# rev2.net
KiCad netlist of a schematic drawn in EAGLE
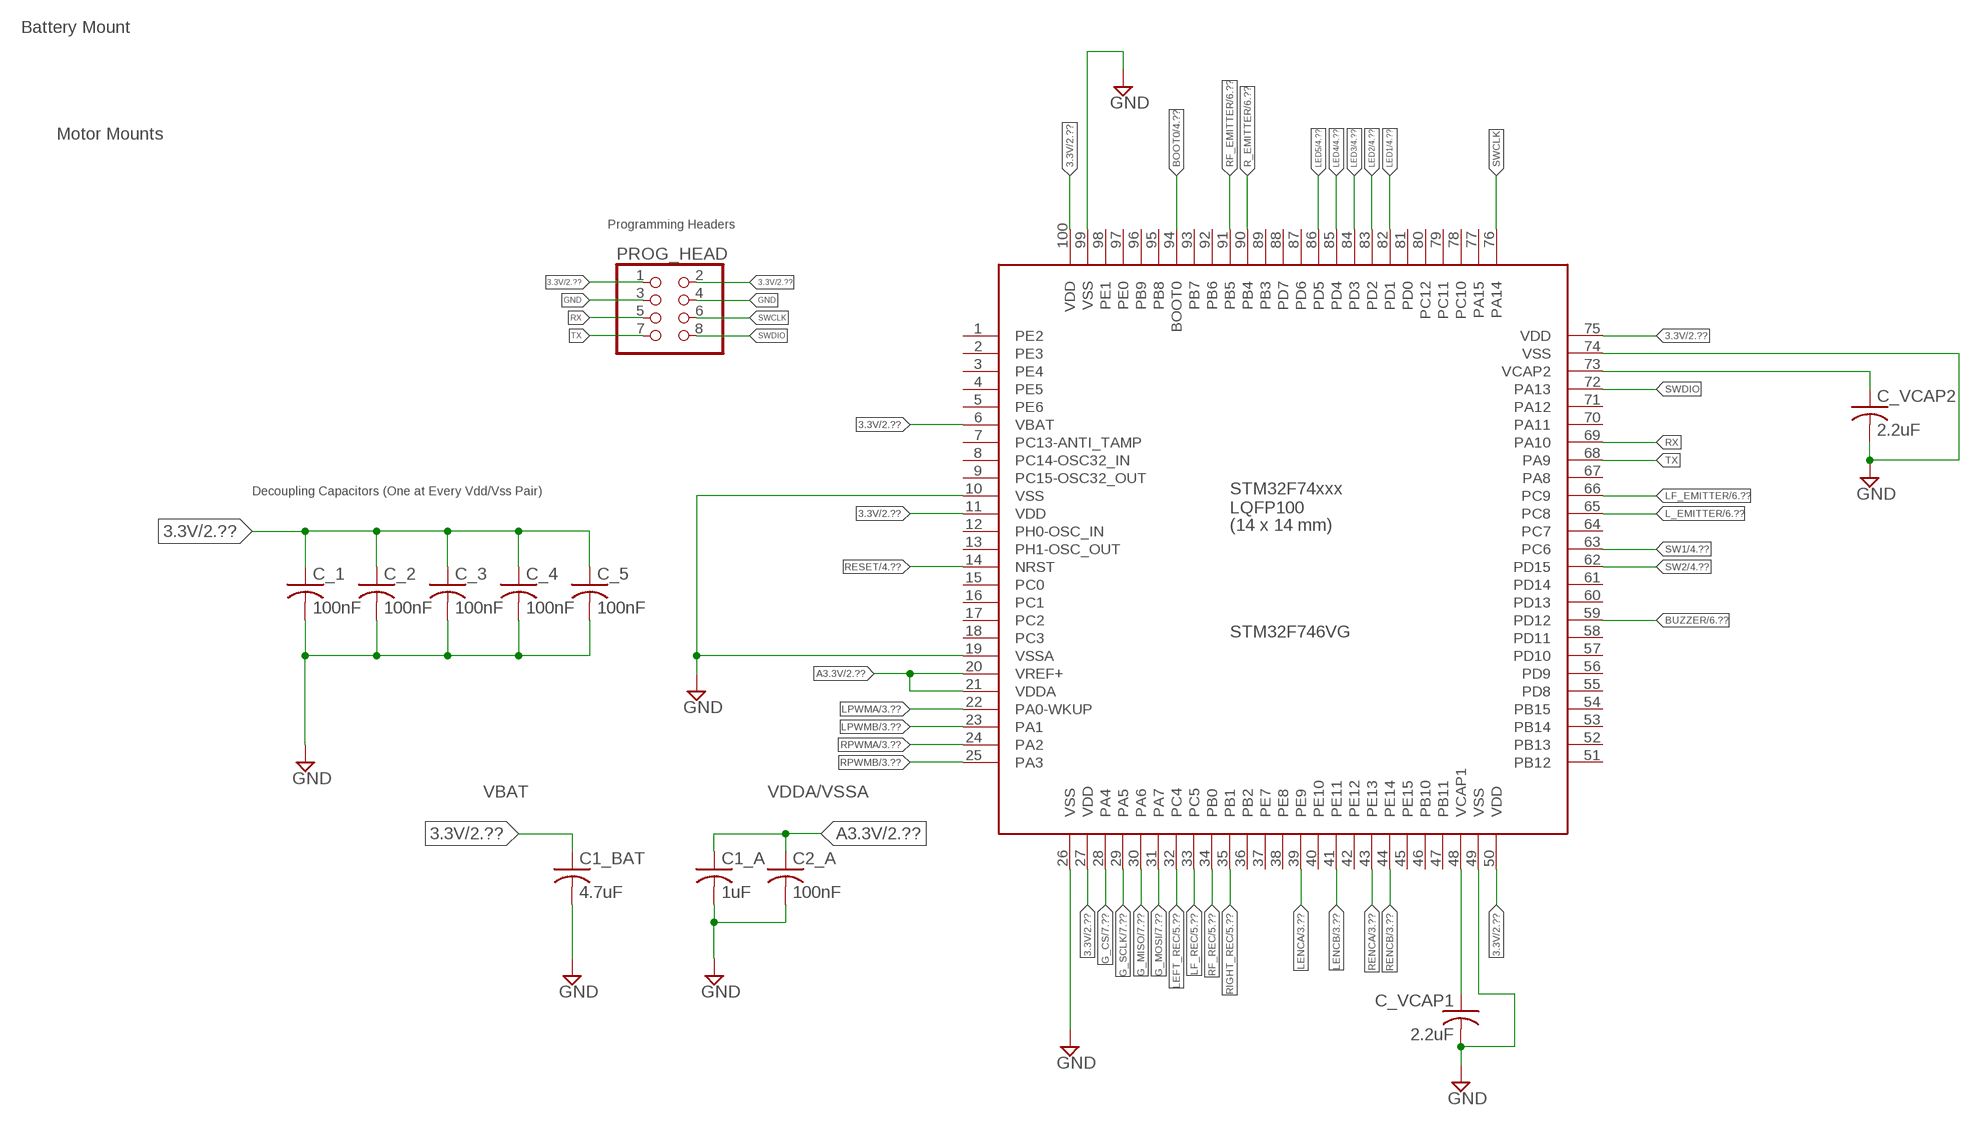
[diagram p0: schematic, sheet 1]
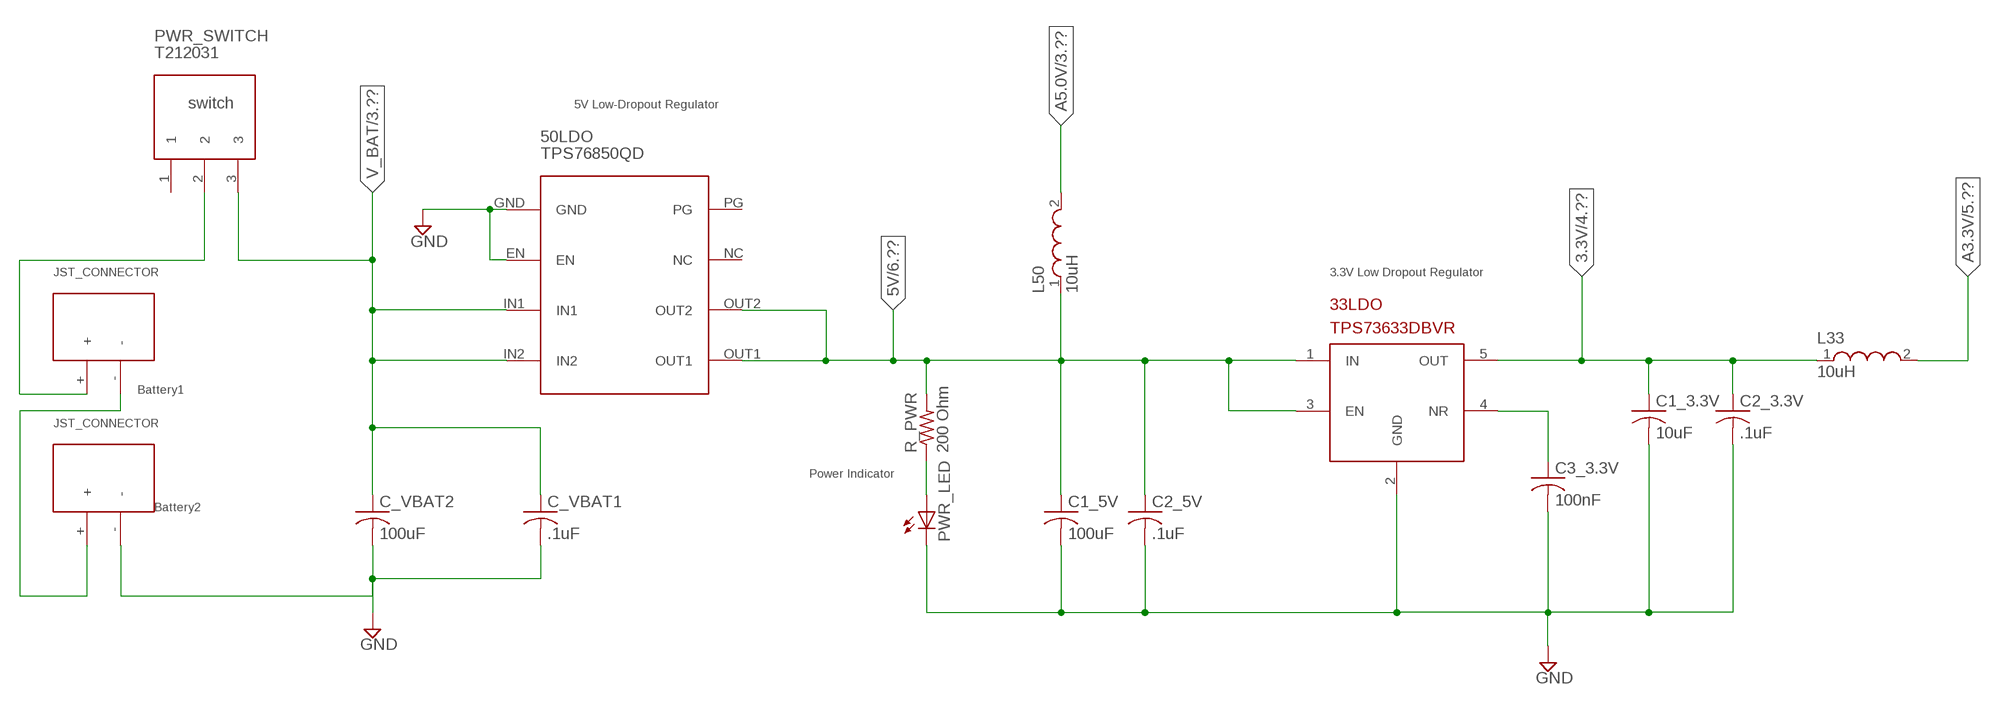
[diagram p1: schematic, sheet 2]
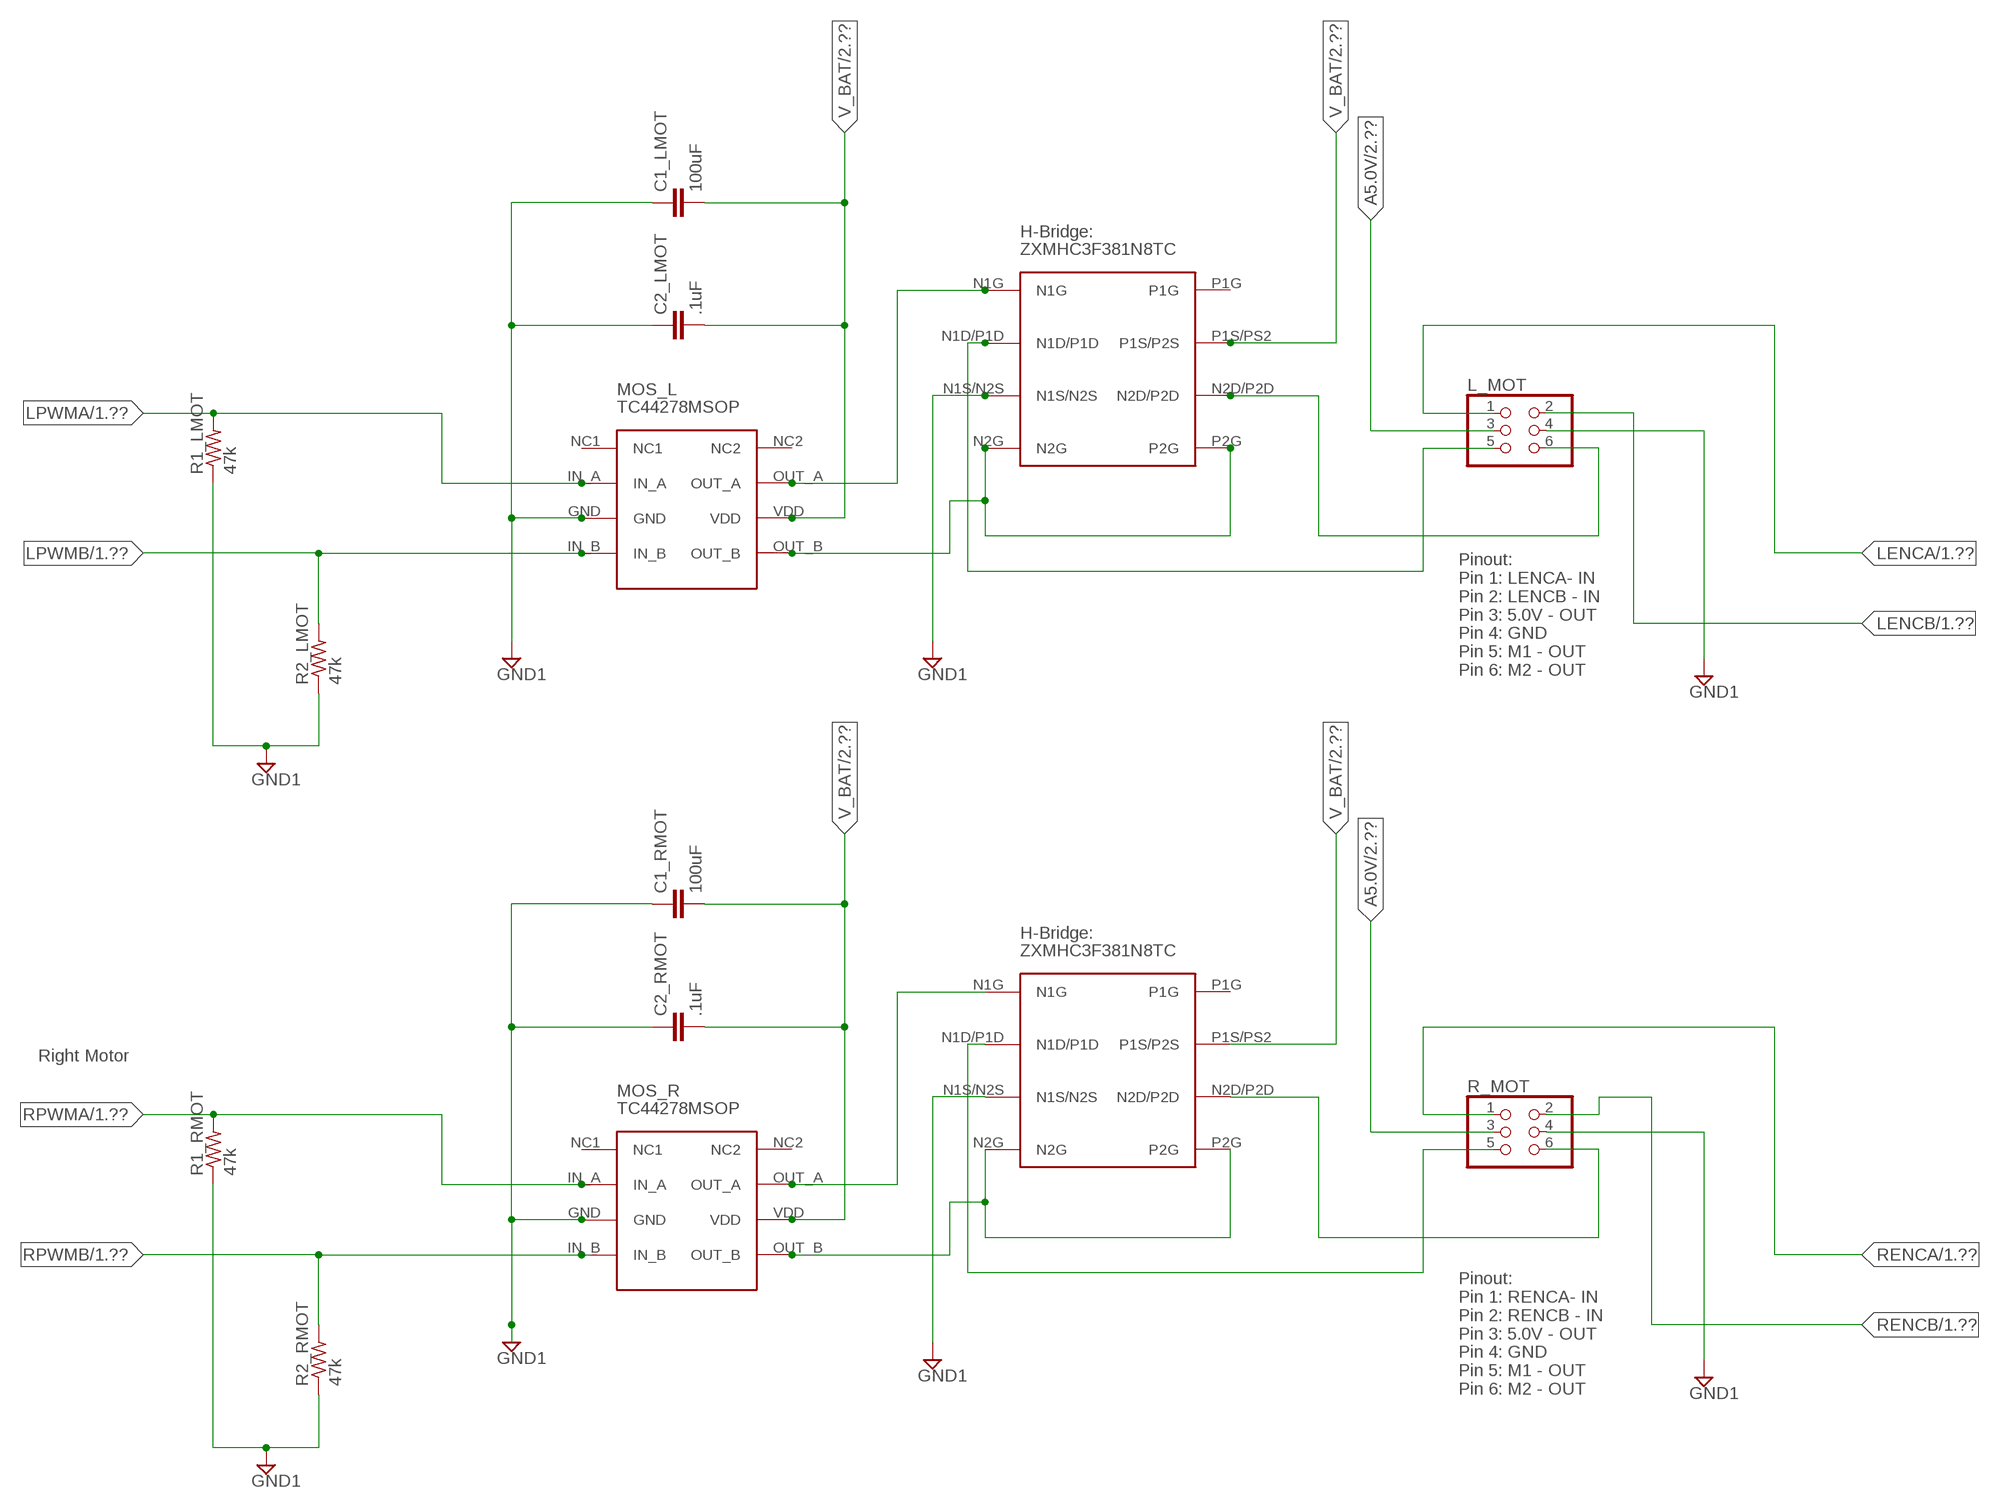
[diagram p2: schematic, sheet 3]
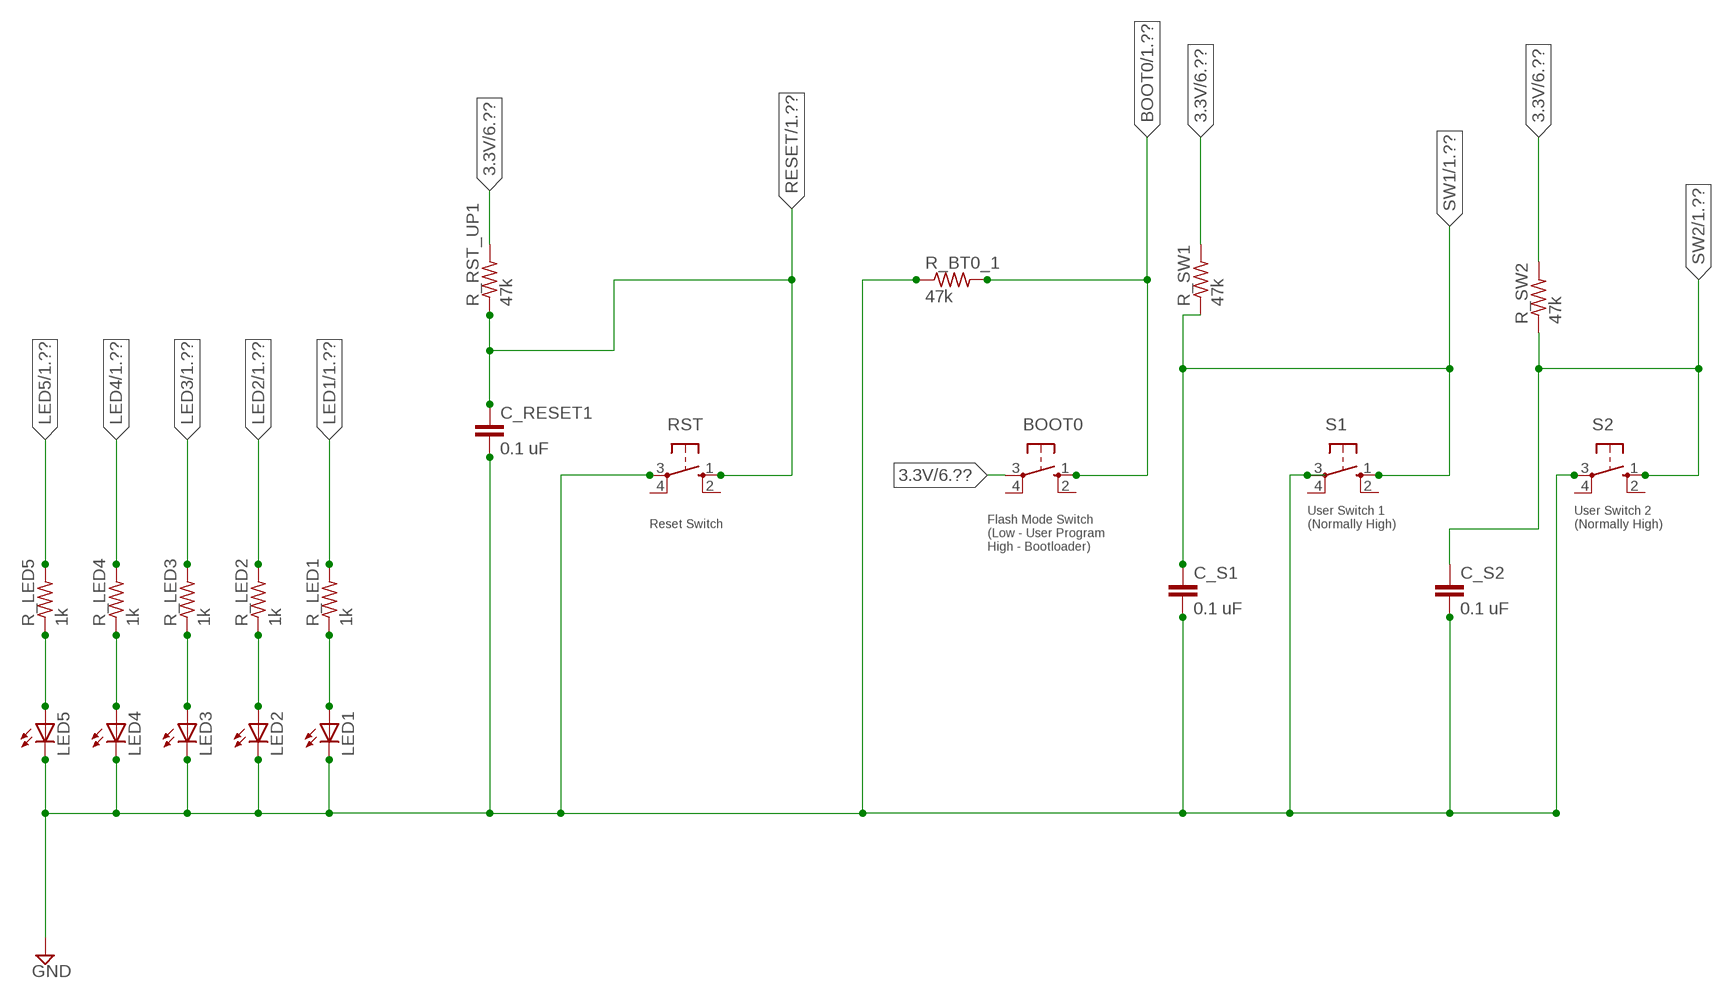
[diagram p3: schematic, sheet 4]
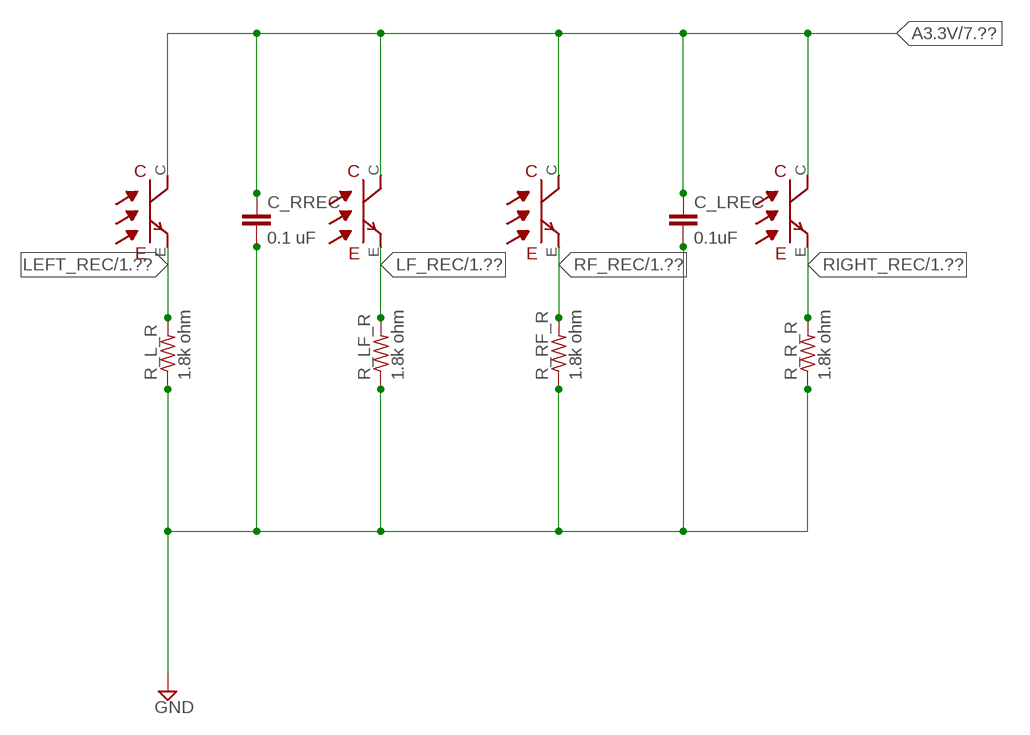
[diagram p4: schematic, sheet 5]
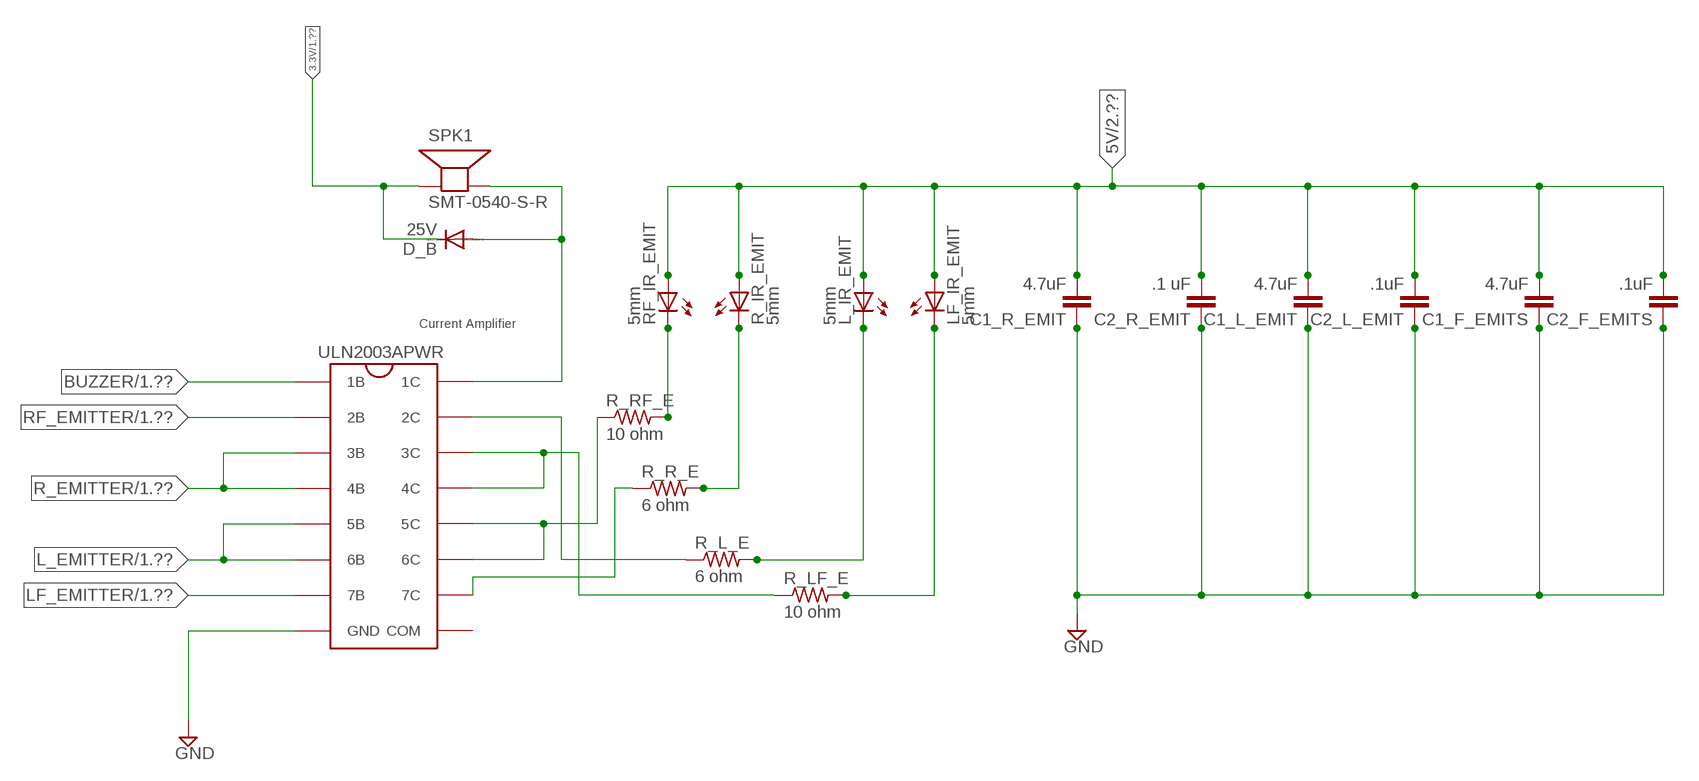
[diagram p5: schematic, sheet 6]
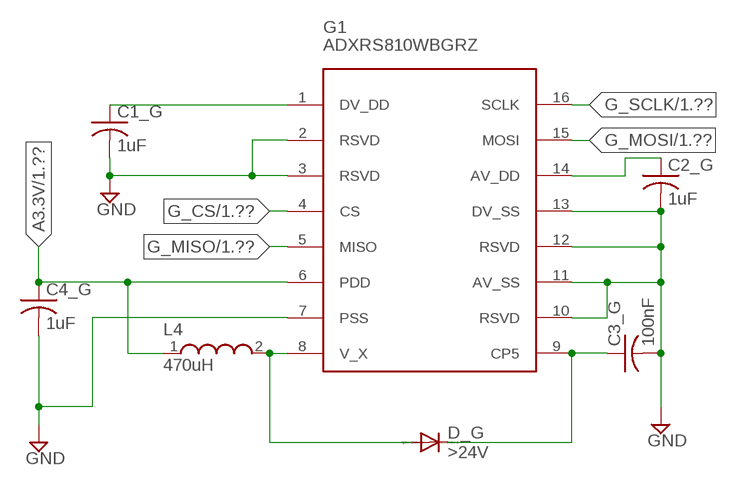
[diagram p6: schematic, sheet 7]

(export (version "E")
  (design (tool "Eeschema 10.0.6"))
  (components
    (comp (ref "C1_LMOT")
      (value "100uF")
      (footprint "eagle-import:C0805")
      (libsource (lib "eagle-import") (part "C-EUC0805"))
    )
    (comp (ref "C1_RMOT")
      (value "100uF")
      (footprint "eagle-import:C0805")
      (libsource (lib "eagle-import") (part "C-EUC0805"))
    )
    (comp (ref "C2_LMOT")
      (value ".1uF")
      (footprint "eagle-import:C0805")
      (libsource (lib "eagle-import") (part "C-EUC0805"))
    )
    (comp (ref "C2_RMOT")
      (value ".1uF")
      (footprint "eagle-import:C0805")
      (libsource (lib "eagle-import") (part "C-EUC0805"))
    )
    (comp (ref "HB_L")
      (value "ZXMHC3F381N8TC")
      (footprint "eagle-import:8-SOIC")
      (libsource (lib "eagle-import") (part "ZXMHC3F381N8TC"))
    )
    (comp (ref "HB_R")
      (value "ZXMHC3F381N8TC")
      (footprint "eagle-import:8-SOIC")
      (libsource (lib "eagle-import") (part "ZXMHC3F381N8TC"))
    )
    (comp (ref "L_MOT")
      (value "PINHD-2X3")
      (footprint "eagle-import:2X03")
      (libsource (lib "eagle-import") (part "PINHD-2X3"))
    )
    (comp (ref "MOS_L")
      (value "TC44278MSOP")
      (footprint "eagle-import:TC44278MSOP")
      (libsource (lib "eagle-import") (part "TC44278MSOP"))
    )
    (comp (ref "MOS_R")
      (value "TC44278MSOP")
      (footprint "eagle-import:TC44278MSOP")
      (libsource (lib "eagle-import") (part "TC44278MSOP"))
    )
    (comp (ref "R1_LMOT")
      (value "47k")
      (footprint "eagle-import:R0603")
      (libsource (lib "eagle-import") (part "R-US_R0603"))
    )
    (comp (ref "R1_RMOT")
      (value "47k")
      (footprint "eagle-import:R0603")
      (libsource (lib "eagle-import") (part "R-US_R0603"))
    )
    (comp (ref "R2_LMOT")
      (value "47k")
      (footprint "eagle-import:R0603")
      (libsource (lib "eagle-import") (part "R-US_R0603"))
    )
    (comp (ref "R2_RMOT")
      (value "47k")
      (footprint "eagle-import:R0603")
      (libsource (lib "eagle-import") (part "R-US_R0603"))
    )
    (comp (ref "R_MOT")
      (value "PINHD-2X3")
      (footprint "eagle-import:2X03")
      (libsource (lib "eagle-import") (part "PINHD-2X3"))
    )
    (comp (ref "C1_F_EMITS")
      (value "4.7uF")
      (footprint "eagle-import:C0603")
      (libsource (lib "eagle-import") (part "resistor_C-EUC0603"))
    )
    (comp (ref "C1_L_EMIT")
      (value "4.7uF")
      (footprint "eagle-import:C0603")
      (libsource (lib "eagle-import") (part "resistor_C-EUC0603"))
    )
    (comp (ref "C1_R_EMIT")
      (value "4.7uF")
      (footprint "eagle-import:C0603")
      (libsource (lib "eagle-import") (part "resistor_C-EUC0603"))
    )
    (comp (ref "C2_F_EMITS")
      (value ".1uF")
      (footprint "eagle-import:C0603")
      (libsource (lib "eagle-import") (part "resistor_C-EUC0603"))
    )
    (comp (ref "C2_L_EMIT")
      (value ".1uF")
      (footprint "eagle-import:C0603")
      (libsource (lib "eagle-import") (part "resistor_C-EUC0603"))
    )
    (comp (ref "C2_R_EMIT")
      (value ".1 uF")
      (footprint "eagle-import:C0603")
      (libsource (lib "eagle-import") (part "resistor_C-EUC0603"))
    )
    (comp (ref "D_B")
      (value "25V")
      (footprint "eagle-import:SOD123")
      (libsource (lib "eagle-import") (part "DIODE-SOD123"))
    )
    (comp (ref "LF_IR_EMIT")
      (value "5mm")
      (footprint "eagle-import:LED5MM")
      (libsource (lib "eagle-import") (part "LED5MM"))
    )
    (comp (ref "L_IR_EMIT")
      (value "5mm")
      (footprint "eagle-import:LED5MM")
      (libsource (lib "eagle-import") (part "LED5MM"))
    )
    (comp (ref "RF_IR_EMIT")
      (value "5mm")
      (footprint "eagle-import:LED5MM")
      (libsource (lib "eagle-import") (part "LED5MM"))
    )
    (comp (ref "R_IR_EMIT")
      (value "5mm")
      (footprint "eagle-import:LED5MM")
      (libsource (lib "eagle-import") (part "LED5MM"))
    )
    (comp (ref "R_LF_E")
      (value "10 ohm")
      (footprint "eagle-import:R0603")
      (libsource (lib "eagle-import") (part "R-US_R0603"))
    )
    (comp (ref "R_L_E")
      (value "6 ohm")
      (footprint "eagle-import:R0603")
      (libsource (lib "eagle-import") (part "R-US_R0603"))
    )
    (comp (ref "R_RF_E")
      (value "10 ohm")
      (footprint "eagle-import:R0603")
      (libsource (lib "eagle-import") (part "R-US_R0603"))
    )
    (comp (ref "R_R_E")
      (value "6 ohm")
      (footprint "eagle-import:R0603")
      (libsource (lib "eagle-import") (part "R-US_R0603"))
    )
    (comp (ref "SPK1")
      (value "SMT-0540-S-R")
      (footprint "eagle-import:SMT-0540-S-R")
      (fields (field (name "MF") "PUI Audio"))
      (libsource (lib "eagle-import") (part "SMT-0540-S-R"))
    )
    (comp (ref "U$9")
      (value "ULN2003APWR")
      (footprint "eagle-import:ULN2003APWR")
      (libsource (lib "eagle-import") (part "ULN2003APWR"))
    )
    (comp (ref "33LDO")
      (value "TPS73633DBVR")
      (footprint "eagle-import:SOT23-DBV")
      (fields (field (name "MF") "Texas Instruments"))
      (libsource (lib "eagle-import") (part "TPS73633DBVR"))
    )
    (comp (ref "50LDO")
      (value "TPS76850QD")
      (footprint "eagle-import:8-SOIC(SMT)")
      (libsource (lib "eagle-import") (part "TPS76850"))
    )
    (comp (ref "C1_3.3V")
      (value "10uF")
      (footprint "eagle-import:C0603")
      (libsource (lib "eagle-import") (part "resistor_C-USC0603"))
    )
    (comp (ref "C1_5V")
      (value "100uF")
      (footprint "eagle-import:C0603")
      (libsource (lib "eagle-import") (part "resistor_C-USC0603"))
    )
    (comp (ref "C2_3.3V")
      (value ".1uF")
      (footprint "eagle-import:C0603")
      (libsource (lib "eagle-import") (part "resistor_C-USC0603"))
    )
    (comp (ref "C2_5V")
      (value ".1uF")
      (footprint "eagle-import:C0603")
      (libsource (lib "eagle-import") (part "resistor_C-USC0603"))
    )
    (comp (ref "C3_3.3V")
      (value "100nF")
      (footprint "eagle-import:C0603")
      (libsource (lib "eagle-import") (part "resistor_C-USC0603"))
    )
    (comp (ref "C_VBAT1")
      (value ".1uF")
      (footprint "eagle-import:C0603")
      (libsource (lib "eagle-import") (part "resistor_C-USC0603"))
    )
    (comp (ref "C_VBAT2")
      (value "100uF")
      (footprint "eagle-import:C1206")
      (libsource (lib "eagle-import") (part "resistor_C-USC1206"))
    )
    (comp (ref "L33")
      (value "10uH")
      (footprint "eagle-import:WE-MI_0805")
      (libsource (lib "eagle-import") (part "WE-MI_0805"))
    )
    (comp (ref "L50")
      (value "10uH")
      (footprint "eagle-import:WE-MI_0805")
      (libsource (lib "eagle-import") (part "WE-MI_0805"))
    )
    (comp (ref "PWR_LED")
      (value "LEDCHIPLED_0805")
      (footprint "eagle-import:CHIPLED_0805")
      (libsource (lib "eagle-import") (part "LEDCHIPLED_0805"))
    )
    (comp (ref "PWR_SWITCH")
      (value "T212031")
      (footprint "eagle-import:T212031")
      (libsource (lib "eagle-import") (part "T212031"))
    )
    (comp (ref "R_PWR")
      (value "200 Ohm")
      (footprint "eagle-import:R0603")
      (libsource (lib "eagle-import") (part "R-US_R0603"))
    )
    (comp (ref "U$7")
      (value "JST_CONNECTOR_FEMALE")
      (footprint "eagle-import:JST_CONNECTOR_FEMALE")
      (libsource (lib "eagle-import") (part "JST_CONNECTOR_FEMALE"))
    )
    (comp (ref "U$8")
      (value "JST_CONNECTOR_FEMALE")
      (footprint "eagle-import:JST_CONNECTOR_FEMALE")
      (libsource (lib "eagle-import") (part "JST_CONNECTOR_FEMALE"))
    )
    (comp (ref "C_LREC")
      (value "0.1uF")
      (footprint "eagle-import:C0603")
      (libsource (lib "eagle-import") (part "resistor_C-EUC0603"))
    )
    (comp (ref "C_RREC")
      (value "0.1 uF")
      (footprint "eagle-import:C0603")
      (libsource (lib "eagle-import") (part "resistor_C-EUC0603"))
    )
    (comp (ref "LF_REC")
      (value "RECEIVER")
      (footprint "eagle-import:RECEIVER")
      (libsource (lib "eagle-import") (part "RECEIVER"))
    )
    (comp (ref "L_REC")
      (value "RECEIVER")
      (footprint "eagle-import:RECEIVER")
      (libsource (lib "eagle-import") (part "RECEIVER"))
    )
    (comp (ref "RF_REC")
      (value "RECEIVER")
      (footprint "eagle-import:RECEIVER")
      (libsource (lib "eagle-import") (part "RECEIVER"))
    )
    (comp (ref "R_LF_R")
      (value "1.8k ohm")
      (footprint "eagle-import:R0603")
      (libsource (lib "eagle-import") (part "R-US_R0603"))
    )
    (comp (ref "R_L_R")
      (value "1.8k ohm")
      (footprint "eagle-import:R0603")
      (libsource (lib "eagle-import") (part "R-US_R0603"))
    )
    (comp (ref "R_REC")
      (value "RECEIVER")
      (footprint "eagle-import:RECEIVER")
      (libsource (lib "eagle-import") (part "RECEIVER"))
    )
    (comp (ref "R_RF_R")
      (value "1.8k ohm")
      (footprint "eagle-import:R0603")
      (libsource (lib "eagle-import") (part "R-US_R0603"))
    )
    (comp (ref "R_R_R")
      (value "1.8k ohm")
      (footprint "eagle-import:R0603")
      (libsource (lib "eagle-import") (part "R-US_R0603"))
    )
    (comp (ref "C1_G")
      (value "1uF")
      (footprint "eagle-import:C0603")
      (libsource (lib "eagle-import") (part "C-USC0603"))
    )
    (comp (ref "C2_G")
      (value "1uF")
      (footprint "eagle-import:C0603")
      (libsource (lib "eagle-import") (part "C-USC0603"))
    )
    (comp (ref "C3_G")
      (value "100nF")
      (footprint "eagle-import:C0603")
      (libsource (lib "eagle-import") (part "C-USC0603"))
    )
    (comp (ref "C4_G")
      (value "1uF")
      (footprint "eagle-import:C0603")
      (libsource (lib "eagle-import") (part "C-USC0603"))
    )
    (comp (ref "D_G")
      (value ">24V")
      (footprint "eagle-import:SOD123")
      (libsource (lib "eagle-import") (part "DIODE-SOD123"))
    )
    (comp (ref "G1")
      (value "ADXRS810")
      (footprint "eagle-import:SOIC-16")
      (libsource (lib "eagle-import") (part "ADXRS810"))
    )
    (comp (ref "L4")
      (value "470uH")
      (footprint "eagle-import:WE-MI_0805")
      (libsource (lib "eagle-import") (part "WE-MI_0805"))
    )
    (comp (ref "C1_A")
      (value "1uF")
      (footprint "eagle-import:C0603")
      (libsource (lib "eagle-import") (part "C-USC0603"))
    )
    (comp (ref "C1_BAT")
      (value "4.7uF")
      (footprint "eagle-import:C0603")
      (libsource (lib "eagle-import") (part "C-USC0603"))
    )
    (comp (ref "C2_A")
      (value "100nF")
      (footprint "eagle-import:C0603")
      (libsource (lib "eagle-import") (part "C-USC0603"))
    )
    (comp (ref "C_1")
      (value "100nF")
      (footprint "eagle-import:C0603")
      (libsource (lib "eagle-import") (part "C-USC0603"))
    )
    (comp (ref "C_2")
      (value "100nF")
      (footprint "eagle-import:C0603")
      (libsource (lib "eagle-import") (part "C-USC0603"))
    )
    (comp (ref "C_3")
      (value "100nF")
      (footprint "eagle-import:C0603")
      (libsource (lib "eagle-import") (part "C-USC0603"))
    )
    (comp (ref "C_4")
      (value "100nF")
      (footprint "eagle-import:C0603")
      (libsource (lib "eagle-import") (part "C-USC0603"))
    )
    (comp (ref "C_5")
      (value "100nF")
      (footprint "eagle-import:C0603")
      (libsource (lib "eagle-import") (part "C-USC0603"))
    )
    (comp (ref "C_VCAP1")
      (value "2.2uF")
      (footprint "eagle-import:C0603")
      (libsource (lib "eagle-import") (part "C-USC0603"))
    )
    (comp (ref "C_VCAP2")
      (value "2.2uF")
      (footprint "eagle-import:C0603")
      (libsource (lib "eagle-import") (part "C-USC0603"))
    )
    (comp (ref "PROG_HEAD")
      (value "PINHD-2X4")
      (footprint "eagle-import:2X04")
      (libsource (lib "eagle-import") (part "PINHD-2X4"))
    )
    (comp (ref "U$2")
      (value "MOTOR")
      (footprint "eagle-import:MOTOR_MOUNT")
      (libsource (lib "eagle-import") (part "MOTOR"))
    )
    (comp (ref "U$3")
      (value "STM32F746VG")
      (footprint "eagle-import:LQFP100")
      (libsource (lib "eagle-import") (part "STM32F769VG-1"))
    )
    (comp (ref "BOOT0")
      (value "10-XX")
      (footprint "eagle-import:B3F-10XX")
      (fields (field (name "MPN") "B3F-1000"))
      (libsource (lib "eagle-import") (part "10-XX"))
    )
    (comp (ref "C_RESET1")
      (value "0.1 uF")
      (footprint "eagle-import:C0603")
      (libsource (lib "eagle-import") (part "resistor_C-EUC0603"))
    )
    (comp (ref "C_S1")
      (value "0.1 uF")
      (footprint "eagle-import:C0603")
      (libsource (lib "eagle-import") (part "resistor_C-EUC0603"))
    )
    (comp (ref "C_S2")
      (value "0.1 uF")
      (footprint "eagle-import:C0603")
      (libsource (lib "eagle-import") (part "resistor_C-EUC0603"))
    )
    (comp (ref "LED1")
      (value "LEDCHIPLED_0805")
      (footprint "eagle-import:CHIPLED_0805")
      (libsource (lib "eagle-import") (part "LEDCHIPLED_0805"))
    )
    (comp (ref "LED2")
      (value "LEDCHIPLED_0805")
      (footprint "eagle-import:CHIPLED_0805")
      (libsource (lib "eagle-import") (part "LEDCHIPLED_0805"))
    )
    (comp (ref "LED3")
      (value "LEDCHIPLED_0805")
      (footprint "eagle-import:CHIPLED_0805")
      (libsource (lib "eagle-import") (part "LEDCHIPLED_0805"))
    )
    (comp (ref "LED4")
      (value "LEDCHIPLED_0805")
      (footprint "eagle-import:CHIPLED_0805")
      (libsource (lib "eagle-import") (part "LEDCHIPLED_0805"))
    )
    (comp (ref "LED5")
      (value "LEDCHIPLED_0805")
      (footprint "eagle-import:CHIPLED_0805")
      (libsource (lib "eagle-import") (part "LEDCHIPLED_0805"))
    )
    (comp (ref "RST")
      (value "10-XX")
      (footprint "eagle-import:B3F-10XX")
      (fields (field (name "MPN") "B3F-1000"))
      (libsource (lib "eagle-import") (part "10-XX"))
    )
    (comp (ref "R_BT0_1")
      (value "47k")
      (footprint "eagle-import:R0603")
      (libsource (lib "eagle-import") (part "R-US_R0603"))
    )
    (comp (ref "R_LED1")
      (value "1k")
      (footprint "eagle-import:R0603")
      (libsource (lib "eagle-import") (part "R-US_R0603"))
    )
    (comp (ref "R_LED2")
      (value "1k")
      (footprint "eagle-import:R0603")
      (libsource (lib "eagle-import") (part "R-US_R0603"))
    )
    (comp (ref "R_LED3")
      (value "1k")
      (footprint "eagle-import:R0603")
      (libsource (lib "eagle-import") (part "R-US_R0603"))
    )
    (comp (ref "R_LED4")
      (value "1k")
      (footprint "eagle-import:R0603")
      (libsource (lib "eagle-import") (part "R-US_R0603"))
    )
    (comp (ref "R_LED5")
      (value "1k")
      (footprint "eagle-import:R0603")
      (libsource (lib "eagle-import") (part "R-US_R0603"))
    )
    (comp (ref "R_RST_UP1")
      (value "47k")
      (footprint "eagle-import:R0603")
      (libsource (lib "eagle-import") (part "R-US_R0603"))
    )
    (comp (ref "R_SW1")
      (value "47k")
      (footprint "eagle-import:R0603")
      (libsource (lib "eagle-import") (part "R-US_R0603"))
    )
    (comp (ref "R_SW2")
      (value "47k")
      (footprint "eagle-import:R0603")
      (libsource (lib "eagle-import") (part "R-US_R0603"))
    )
    (comp (ref "S1")
      (value "10-XX")
      (footprint "eagle-import:B3F-10XX")
      (fields (field (name "MPN") "B3F-1000"))
      (libsource (lib "eagle-import") (part "10-XX"))
    )
    (comp (ref "S2")
      (value "10-XX")
      (footprint "eagle-import:B3F-10XX")
      (fields (field (name "MPN") "B3F-1000"))
      (libsource (lib "eagle-import") (part "10-XX"))
    )
  )
  (nets
    (net (code "1") (name "3.3V") (class "Default")
      (node (ref "33LDO") (pin "5") (pinfunction "OUT_5") (pintype "bidirectional"))
      (node (ref "BOOT0") (pin "3") (pinfunction "P_3") (pintype "passive"))
      (node (ref "C1_3.3V") (pin "1") (pinfunction "1_1") (pintype "passive"))
      (node (ref "C1_BAT") (pin "1") (pinfunction "1_1") (pintype "passive"))
      (node (ref "C2_3.3V") (pin "1") (pinfunction "1_1") (pintype "passive"))
      (node (ref "C_1") (pin "1") (pinfunction "1_1") (pintype "passive"))
      (node (ref "C_2") (pin "1") (pinfunction "1_1") (pintype "passive"))
      (node (ref "C_3") (pin "1") (pinfunction "1_1") (pintype "passive"))
      (node (ref "C_4") (pin "1") (pinfunction "1_1") (pintype "passive"))
      (node (ref "C_5") (pin "1") (pinfunction "1_1") (pintype "passive"))
      (node (ref "D_B") (pin "C") (pinfunction "C_C") (pintype "passive"))
      (node (ref "L33") (pin "1") (pinfunction "1_1") (pintype "passive"))
      (node (ref "PROG_HEAD") (pin "1") (pinfunction "1_1") (pintype "passive"))
      (node (ref "PROG_HEAD") (pin "2") (pinfunction "2_2") (pintype "passive"))
      (node (ref "R_RST_UP1") (pin "2") (pinfunction "2_2") (pintype "passive"))
      (node (ref "R_SW1") (pin "2") (pinfunction "2_2") (pintype "passive"))
      (node (ref "R_SW2") (pin "2") (pinfunction "2_2") (pintype "passive"))
      (node (ref "SPK1") (pin "-") (pinfunction "+_-") (pintype "passive"))
      (node (ref "U$3") (pin "100") (pinfunction "VDD_100") (pintype "bidirectional"))
      (node (ref "U$3") (pin "11") (pinfunction "VDD_11") (pintype "bidirectional"))
      (node (ref "U$3") (pin "27") (pinfunction "VDD_27") (pintype "bidirectional"))
      (node (ref "U$3") (pin "50") (pinfunction "VDD_50") (pintype "bidirectional"))
      (node (ref "U$3") (pin "6") (pinfunction "VBAT_6") (pintype "bidirectional"))
      (node (ref "U$3") (pin "75") (pinfunction "VDD_75") (pintype "bidirectional"))
    )
    (net (code "2") (name "5V") (class "Default")
      (node (ref "33LDO") (pin "1") (pinfunction "IN_1") (pintype "bidirectional"))
      (node (ref "33LDO") (pin "3") (pinfunction "EN_3") (pintype "bidirectional"))
      (node (ref "50LDO") (pin "OUT1") (pinfunction "OUT1_OUT1") (pintype "bidirectional"))
      (node (ref "50LDO") (pin "OUT2") (pinfunction "OUT2_OUT2") (pintype "bidirectional"))
      (node (ref "C1_5V") (pin "1") (pinfunction "1_1") (pintype "passive"))
      (node (ref "C1_F_EMITS") (pin "2") (pinfunction "2_2") (pintype "passive"))
      (node (ref "C1_L_EMIT") (pin "2") (pinfunction "2_2") (pintype "passive"))
      (node (ref "C1_R_EMIT") (pin "2") (pinfunction "2_2") (pintype "passive"))
      (node (ref "C2_5V") (pin "1") (pinfunction "1_1") (pintype "passive"))
      (node (ref "C2_F_EMITS") (pin "2") (pinfunction "2_2") (pintype "passive"))
      (node (ref "C2_L_EMIT") (pin "2") (pinfunction "2_2") (pintype "passive"))
      (node (ref "C2_R_EMIT") (pin "2") (pinfunction "2_2") (pintype "passive"))
      (node (ref "L50") (pin "1") (pinfunction "1_1") (pintype "passive"))
      (node (ref "LF_IR_EMIT") (pin "A") (pinfunction "A_A") (pintype "passive"))
      (node (ref "L_IR_EMIT") (pin "A") (pinfunction "A_A") (pintype "passive"))
      (node (ref "RF_IR_EMIT") (pin "A") (pinfunction "A_A") (pintype "passive"))
      (node (ref "R_IR_EMIT") (pin "A") (pinfunction "A_A") (pintype "passive"))
      (node (ref "R_PWR") (pin "2") (pinfunction "2_2") (pintype "passive"))
    )
    (net (code "3") (name "A3.3V") (class "Default")
      (node (ref "C1_A") (pin "1") (pinfunction "1_1") (pintype "passive"))
      (node (ref "C2_A") (pin "1") (pinfunction "1_1") (pintype "passive"))
      (node (ref "C4_G") (pin "1") (pinfunction "1_1") (pintype "passive"))
      (node (ref "C_LREC") (pin "1") (pinfunction "1_1") (pintype "passive"))
      (node (ref "C_RREC") (pin "1") (pinfunction "1_1") (pintype "passive"))
      (node (ref "G1") (pin "6") (pinfunction "PDD_6") (pintype "bidirectional"))
      (node (ref "L33") (pin "2") (pinfunction "2_2") (pintype "passive"))
      (node (ref "L4") (pin "1") (pinfunction "1_1") (pintype "passive"))
      (node (ref "LF_REC") (pin "C") (pinfunction "C_C") (pintype "bidirectional"))
      (node (ref "L_REC") (pin "C") (pinfunction "C_C") (pintype "bidirectional"))
      (node (ref "RF_REC") (pin "C") (pinfunction "C_C") (pintype "bidirectional"))
      (node (ref "R_REC") (pin "C") (pinfunction "C_C") (pintype "bidirectional"))
      (node (ref "U$3") (pin "20") (pinfunction "VREF+_20") (pintype "bidirectional"))
      (node (ref "U$3") (pin "21") (pinfunction "VDDA_21") (pintype "bidirectional"))
    )
    (net (code "4") (name "A5.0V") (class "Default")
      (node (ref "L50") (pin "2") (pinfunction "2_2") (pintype "passive"))
      (node (ref "L_MOT") (pin "3") (pinfunction "3_3") (pintype "passive"))
      (node (ref "R_MOT") (pin "3") (pinfunction "3_3") (pintype "passive"))
    )
    (net (code "5") (name "BOOT0") (class "Default")
      (node (ref "BOOT0") (pin "1") (pinfunction "S_1") (pintype "passive"))
      (node (ref "R_BT0_1") (pin "2") (pinfunction "2_2") (pintype "passive"))
      (node (ref "U$3") (pin "94") (pinfunction "BOOT0_94") (pintype "bidirectional"))
    )
    (net (code "6") (name "BUZZER") (class "Default")
      (node (ref "U$3") (pin "59") (pinfunction "PD12_59") (pintype "bidirectional"))
      (node (ref "U$9") (pin "1B") (pinfunction "1B_1B") (pintype "bidirectional"))
    )
    (net (code "7") (name "GND") (class "Default")
      (node (ref "33LDO") (pin "2") (pinfunction "GND_2") (pintype "bidirectional"))
      (node (ref "50LDO") (pin "EN") (pinfunction "EN_EN") (pintype "bidirectional"))
      (node (ref "50LDO") (pin "GND") (pinfunction "GND_GND") (pintype "bidirectional"))
      (node (ref "C1_3.3V") (pin "2") (pinfunction "2_2") (pintype "passive"))
      (node (ref "C1_5V") (pin "2") (pinfunction "2_2") (pintype "passive"))
      (node (ref "C1_A") (pin "2") (pinfunction "2_2") (pintype "passive"))
      (node (ref "C1_BAT") (pin "2") (pinfunction "2_2") (pintype "passive"))
      (node (ref "C1_F_EMITS") (pin "1") (pinfunction "1_1") (pintype "passive"))
      (node (ref "C1_G") (pin "2") (pinfunction "2_2") (pintype "passive"))
      (node (ref "C1_LMOT") (pin "1") (pinfunction "1_1") (pintype "passive"))
      (node (ref "C1_L_EMIT") (pin "1") (pinfunction "1_1") (pintype "passive"))
      (node (ref "C1_RMOT") (pin "1") (pinfunction "1_1") (pintype "passive"))
      (node (ref "C1_R_EMIT") (pin "1") (pinfunction "1_1") (pintype "passive"))
      (node (ref "C2_3.3V") (pin "2") (pinfunction "2_2") (pintype "passive"))
      (node (ref "C2_5V") (pin "2") (pinfunction "2_2") (pintype "passive"))
      (node (ref "C2_A") (pin "2") (pinfunction "2_2") (pintype "passive"))
      (node (ref "C2_F_EMITS") (pin "1") (pinfunction "1_1") (pintype "passive"))
      (node (ref "C2_G") (pin "2") (pinfunction "2_2") (pintype "passive"))
      (node (ref "C2_LMOT") (pin "1") (pinfunction "1_1") (pintype "passive"))
      (node (ref "C2_L_EMIT") (pin "1") (pinfunction "1_1") (pintype "passive"))
      (node (ref "C2_RMOT") (pin "1") (pinfunction "1_1") (pintype "passive"))
      (node (ref "C2_R_EMIT") (pin "1") (pinfunction "1_1") (pintype "passive"))
      (node (ref "C3_3.3V") (pin "2") (pinfunction "2_2") (pintype "passive"))
      (node (ref "C3_G") (pin "2") (pinfunction "2_2") (pintype "passive"))
      (node (ref "C4_G") (pin "2") (pinfunction "2_2") (pintype "passive"))
      (node (ref "C_1") (pin "2") (pinfunction "2_2") (pintype "passive"))
      (node (ref "C_2") (pin "2") (pinfunction "2_2") (pintype "passive"))
      (node (ref "C_3") (pin "2") (pinfunction "2_2") (pintype "passive"))
      (node (ref "C_4") (pin "2") (pinfunction "2_2") (pintype "passive"))
      (node (ref "C_5") (pin "2") (pinfunction "2_2") (pintype "passive"))
      (node (ref "C_LREC") (pin "2") (pinfunction "2_2") (pintype "passive"))
      (node (ref "C_RESET1") (pin "2") (pinfunction "2_2") (pintype "passive"))
      (node (ref "C_RREC") (pin "2") (pinfunction "2_2") (pintype "passive"))
      (node (ref "C_S1") (pin "2") (pinfunction "2_2") (pintype "passive"))
      (node (ref "C_S2") (pin "2") (pinfunction "2_2") (pintype "passive"))
      (node (ref "C_VBAT1") (pin "2") (pinfunction "2_2") (pintype "passive"))
      (node (ref "C_VBAT2") (pin "2") (pinfunction "2_2") (pintype "passive"))
      (node (ref "C_VCAP1") (pin "2") (pinfunction "2_2") (pintype "passive"))
      (node (ref "C_VCAP2") (pin "2") (pinfunction "2_2") (pintype "passive"))
      (node (ref "G1") (pin "10") (pinfunction "RSVD_10") (pintype "bidirectional"))
      (node (ref "G1") (pin "11") (pinfunction "AV_SS_11") (pintype "bidirectional"))
      (node (ref "G1") (pin "12") (pinfunction "RSVD_12") (pintype "bidirectional"))
      (node (ref "G1") (pin "13") (pinfunction "DV_SS_13") (pintype "bidirectional"))
      (node (ref "G1") (pin "2") (pinfunction "RSVD_2") (pintype "bidirectional"))
      (node (ref "G1") (pin "3") (pinfunction "RSVD_3") (pintype "bidirectional"))
      (node (ref "G1") (pin "7") (pinfunction "PSS_7") (pintype "bidirectional"))
      (node (ref "HB_L") (pin "N1S/N2S") (pinfunction "N1S/N2S_N1S/N2S") (pintype "bidirectional"))
      (node (ref "HB_R") (pin "N1S/N2S") (pinfunction "N1S/N2S_N1S/N2S") (pintype "bidirectional"))
      (node (ref "LED1") (pin "C") (pinfunction "C_C") (pintype "passive"))
      (node (ref "LED2") (pin "C") (pinfunction "C_C") (pintype "passive"))
      (node (ref "LED3") (pin "C") (pinfunction "C_C") (pintype "passive"))
      (node (ref "LED4") (pin "C") (pinfunction "C_C") (pintype "passive"))
      (node (ref "LED5") (pin "C") (pinfunction "C_C") (pintype "passive"))
      (node (ref "L_MOT") (pin "4") (pinfunction "4_4") (pintype "passive"))
      (node (ref "MOS_L") (pin "GND") (pinfunction "GND_GND") (pintype "bidirectional"))
      (node (ref "MOS_R") (pin "GND") (pinfunction "GND_GND") (pintype "bidirectional"))
      (node (ref "PROG_HEAD") (pin "3") (pinfunction "3_3") (pintype "passive"))
      (node (ref "PROG_HEAD") (pin "4") (pinfunction "4_4") (pintype "passive"))
      (node (ref "PWR_LED") (pin "C") (pinfunction "C_C") (pintype "passive"))
      (node (ref "R1_LMOT") (pin "1") (pinfunction "1_1") (pintype "passive"))
      (node (ref "R1_RMOT") (pin "1") (pinfunction "1_1") (pintype "passive"))
      (node (ref "R2_LMOT") (pin "1") (pinfunction "1_1") (pintype "passive"))
      (node (ref "R2_RMOT") (pin "1") (pinfunction "1_1") (pintype "passive"))
      (node (ref "RST") (pin "3") (pinfunction "P_3") (pintype "passive"))
      (node (ref "R_BT0_1") (pin "1") (pinfunction "1_1") (pintype "passive"))
      (node (ref "R_LF_R") (pin "1") (pinfunction "1_1") (pintype "passive"))
      (node (ref "R_L_R") (pin "1") (pinfunction "1_1") (pintype "passive"))
      (node (ref "R_MOT") (pin "4") (pinfunction "4_4") (pintype "passive"))
      (node (ref "R_RF_R") (pin "1") (pinfunction "1_1") (pintype "passive"))
      (node (ref "R_R_R") (pin "1") (pinfunction "1_1") (pintype "passive"))
      (node (ref "S1") (pin "3") (pinfunction "P_3") (pintype "passive"))
      (node (ref "S2") (pin "3") (pinfunction "P_3") (pintype "passive"))
      (node (ref "U$3") (pin "10") (pinfunction "VSS_10") (pintype "bidirectional"))
      (node (ref "U$3") (pin "19") (pinfunction "VSSA_19") (pintype "bidirectional"))
      (node (ref "U$3") (pin "26") (pinfunction "VSS_26") (pintype "bidirectional"))
      (node (ref "U$3") (pin "49") (pinfunction "VSS_49") (pintype "bidirectional"))
      (node (ref "U$3") (pin "74") (pinfunction "VSS_74") (pintype "bidirectional"))
      (node (ref "U$3") (pin "99") (pinfunction "VSS_99") (pintype "bidirectional"))
      (node (ref "U$8") (pin "-") (pinfunction "-_-") (pintype "bidirectional"))
      (node (ref "U$9") (pin "GND") (pinfunction "GND_GND") (pintype "bidirectional"))
    )
    (net (code "8") (name "G_CS") (class "Default")
      (node (ref "G1") (pin "4") (pinfunction "CS_4") (pintype "bidirectional"))
      (node (ref "U$3") (pin "28") (pinfunction "PA4_28") (pintype "bidirectional"))
    )
    (net (code "9") (name "G_MISO") (class "Default")
      (node (ref "G1") (pin "5") (pinfunction "MISO_5") (pintype "bidirectional"))
      (node (ref "U$3") (pin "30") (pinfunction "PA6_30") (pintype "bidirectional"))
    )
    (net (code "10") (name "G_MOSI") (class "Default")
      (node (ref "G1") (pin "15") (pinfunction "MOSI_15") (pintype "bidirectional"))
      (node (ref "U$3") (pin "31") (pinfunction "PA7_31") (pintype "bidirectional"))
    )
    (net (code "11") (name "G_SCLK") (class "Default")
      (node (ref "G1") (pin "16") (pinfunction "SCLK_16") (pintype "bidirectional"))
      (node (ref "U$3") (pin "29") (pinfunction "PA5_29") (pintype "bidirectional"))
    )
    (net (code "12") (name "LED1") (class "Default")
      (node (ref "R_LED1") (pin "2") (pinfunction "2_2") (pintype "passive"))
      (node (ref "U$3") (pin "82") (pinfunction "PD1_82") (pintype "bidirectional"))
    )
    (net (code "13") (name "LED2") (class "Default")
      (node (ref "R_LED2") (pin "2") (pinfunction "2_2") (pintype "passive"))
      (node (ref "U$3") (pin "83") (pinfunction "PD2_83") (pintype "bidirectional"))
    )
    (net (code "14") (name "LED3") (class "Default")
      (node (ref "R_LED3") (pin "2") (pinfunction "2_2") (pintype "passive"))
      (node (ref "U$3") (pin "84") (pinfunction "PD3_84") (pintype "bidirectional"))
    )
    (net (code "15") (name "LED4") (class "Default")
      (node (ref "R_LED4") (pin "2") (pinfunction "2_2") (pintype "passive"))
      (node (ref "U$3") (pin "85") (pinfunction "PD4_85") (pintype "bidirectional"))
    )
    (net (code "16") (name "LED5") (class "Default")
      (node (ref "R_LED5") (pin "2") (pinfunction "2_2") (pintype "passive"))
      (node (ref "U$3") (pin "86") (pinfunction "PD5_86") (pintype "bidirectional"))
    )
    (net (code "17") (name "LEFT_REC") (class "Default")
      (node (ref "L_REC") (pin "E") (pinfunction "E_E") (pintype "bidirectional"))
      (node (ref "R_L_R") (pin "2") (pinfunction "2_2") (pintype "passive"))
      (node (ref "U$3") (pin "32") (pinfunction "PC4_32") (pintype "bidirectional"))
    )
    (net (code "18") (name "LENCA") (class "Default")
      (node (ref "L_MOT") (pin "1") (pinfunction "1_1") (pintype "passive"))
      (node (ref "U$3") (pin "39") (pinfunction "PE9_39") (pintype "bidirectional"))
    )
    (net (code "19") (name "LENCB") (class "Default")
      (node (ref "L_MOT") (pin "2") (pinfunction "2_2") (pintype "passive"))
      (node (ref "U$3") (pin "41") (pinfunction "PE11_41") (pintype "bidirectional"))
    )
    (net (code "20") (name "LF_EMITTER") (class "Default")
      (node (ref "U$3") (pin "66") (pinfunction "PC9_66") (pintype "bidirectional"))
      (node (ref "U$9") (pin "7B") (pinfunction "7B_7B") (pintype "bidirectional"))
    )
    (net (code "21") (name "LF_REC") (class "Default")
      (node (ref "LF_REC") (pin "E") (pinfunction "E_E") (pintype "bidirectional"))
      (node (ref "R_LF_R") (pin "2") (pinfunction "2_2") (pintype "passive"))
      (node (ref "U$3") (pin "33") (pinfunction "PC5_33") (pintype "bidirectional"))
    )
    (net (code "22") (name "LPWMA") (class "Default")
      (node (ref "MOS_L") (pin "IN_A") (pinfunction "IN_A_IN_A") (pintype "bidirectional"))
      (node (ref "R1_LMOT") (pin "2") (pinfunction "2_2") (pintype "passive"))
      (node (ref "U$3") (pin "22") (pinfunction "PA0-WKUP_22") (pintype "bidirectional"))
    )
    (net (code "23") (name "LPWMB") (class "Default")
      (node (ref "MOS_L") (pin "IN_B") (pinfunction "IN_B_IN_B") (pintype "bidirectional"))
      (node (ref "R2_LMOT") (pin "2") (pinfunction "2_2") (pintype "passive"))
      (node (ref "U$3") (pin "23") (pinfunction "PA1_23") (pintype "bidirectional"))
    )
    (net (code "24") (name "L_EMITTER") (class "Default")
      (node (ref "U$3") (pin "65") (pinfunction "PC8_65") (pintype "bidirectional"))
      (node (ref "U$9") (pin "5B") (pinfunction "5B_5B") (pintype "bidirectional"))
      (node (ref "U$9") (pin "6B") (pinfunction "6B_6B") (pintype "bidirectional"))
    )
    (net (code "25") (name "Net-(33LDO-NR)") (class "Default")
      (node (ref "33LDO") (pin "4") (pinfunction "NR_4") (pintype "bidirectional"))
      (node (ref "C3_3.3V") (pin "1") (pinfunction "1_1") (pintype "passive"))
    )
    (net (code "26") (name "Net-(G1-AV_DD)") (class "Default")
      (node (ref "C2_G") (pin "1") (pinfunction "1_1") (pintype "passive"))
      (node (ref "G1") (pin "14") (pinfunction "AV_DD_14") (pintype "bidirectional"))
    )
    (net (code "27") (name "Net-(G1-CP5)") (class "Default")
      (node (ref "C3_G") (pin "1") (pinfunction "1_1") (pintype "passive"))
      (node (ref "D_G") (pin "C") (pinfunction "C_C") (pintype "passive"))
      (node (ref "G1") (pin "9") (pinfunction "CP5_9") (pintype "bidirectional"))
    )
    (net (code "28") (name "Net-(G1-DV_DD)") (class "Default")
      (node (ref "C1_G") (pin "1") (pinfunction "1_1") (pintype "passive"))
      (node (ref "G1") (pin "1") (pinfunction "DV_DD_1") (pintype "bidirectional"))
    )
    (net (code "29") (name "Net-(G1-V_X)") (class "Default")
      (node (ref "D_G") (pin "A") (pinfunction "A_A") (pintype "passive"))
      (node (ref "G1") (pin "8") (pinfunction "V_X_8") (pintype "bidirectional"))
      (node (ref "L4") (pin "2") (pinfunction "2_2") (pintype "passive"))
    )
    (net (code "30") (name "Net-(HB_L-PadN1D{slash}P1D)") (class "Default")
      (node (ref "HB_L") (pin "N1D/P1D") (pinfunction "N1D/P1D_N1D/P1D") (pintype "bidirectional"))
      (node (ref "L_MOT") (pin "5") (pinfunction "5_5") (pintype "passive"))
    )
    (net (code "31") (name "Net-(HB_L-PadN1G)") (class "Default")
      (node (ref "HB_L") (pin "N1G") (pinfunction "N1G_N1G") (pintype "bidirectional"))
      (node (ref "MOS_L") (pin "OUT_A") (pinfunction "OUT_A_OUT_A") (pintype "bidirectional"))
    )
    (net (code "32") (name "Net-(HB_L-PadN2D{slash}P2D)") (class "Default")
      (node (ref "HB_L") (pin "N2D/P2D") (pinfunction "N2D/P2D_N2D/P2D") (pintype "bidirectional"))
      (node (ref "L_MOT") (pin "6") (pinfunction "6_6") (pintype "passive"))
    )
    (net (code "33") (name "Net-(HB_L-PadN2G)") (class "Default")
      (node (ref "HB_L") (pin "N2G") (pinfunction "N2G_N2G") (pintype "bidirectional"))
      (node (ref "HB_L") (pin "P2G") (pinfunction "P2G_P2G") (pintype "bidirectional"))
      (node (ref "MOS_L") (pin "OUT_B") (pinfunction "OUT_B_OUT_B") (pintype "bidirectional"))
    )
    (net (code "34") (name "Net-(HB_R-PadN1D{slash}P1D)") (class "Default")
      (node (ref "HB_R") (pin "N1D/P1D") (pinfunction "N1D/P1D_N1D/P1D") (pintype "bidirectional"))
      (node (ref "R_MOT") (pin "5") (pinfunction "5_5") (pintype "passive"))
    )
    (net (code "35") (name "Net-(HB_R-PadN1G)") (class "Default")
      (node (ref "HB_R") (pin "N1G") (pinfunction "N1G_N1G") (pintype "bidirectional"))
      (node (ref "MOS_R") (pin "OUT_A") (pinfunction "OUT_A_OUT_A") (pintype "bidirectional"))
    )
    (net (code "36") (name "Net-(HB_R-PadN2D{slash}P2D)") (class "Default")
      (node (ref "HB_R") (pin "N2D/P2D") (pinfunction "N2D/P2D_N2D/P2D") (pintype "bidirectional"))
      (node (ref "R_MOT") (pin "6") (pinfunction "6_6") (pintype "passive"))
    )
    (net (code "37") (name "Net-(HB_R-PadN2G)") (class "Default")
      (node (ref "HB_R") (pin "N2G") (pinfunction "N2G_N2G") (pintype "bidirectional"))
      (node (ref "HB_R") (pin "P2G") (pinfunction "P2G_P2G") (pintype "bidirectional"))
      (node (ref "MOS_R") (pin "OUT_B") (pinfunction "OUT_B_OUT_B") (pintype "bidirectional"))
    )
    (net (code "38") (name "Net-(LED1-PadA)") (class "Default")
      (node (ref "LED1") (pin "A") (pinfunction "A_A") (pintype "passive"))
      (node (ref "R_LED1") (pin "1") (pinfunction "1_1") (pintype "passive"))
    )
    (net (code "39") (name "Net-(LED2-PadA)") (class "Default")
      (node (ref "LED2") (pin "A") (pinfunction "A_A") (pintype "passive"))
      (node (ref "R_LED2") (pin "1") (pinfunction "1_1") (pintype "passive"))
    )
    (net (code "40") (name "Net-(LED3-PadA)") (class "Default")
      (node (ref "LED3") (pin "A") (pinfunction "A_A") (pintype "passive"))
      (node (ref "R_LED3") (pin "1") (pinfunction "1_1") (pintype "passive"))
    )
    (net (code "41") (name "Net-(LED4-PadA)") (class "Default")
      (node (ref "LED4") (pin "A") (pinfunction "A_A") (pintype "passive"))
      (node (ref "R_LED4") (pin "1") (pinfunction "1_1") (pintype "passive"))
    )
    (net (code "42") (name "Net-(LED5-PadA)") (class "Default")
      (node (ref "LED5") (pin "A") (pinfunction "A_A") (pintype "passive"))
      (node (ref "R_LED5") (pin "1") (pinfunction "1_1") (pintype "passive"))
    )
    (net (code "43") (name "Net-(LF_IR_EMIT-C)") (class "Default")
      (node (ref "LF_IR_EMIT") (pin "K") (pinfunction "C_K") (pintype "passive"))
      (node (ref "R_LF_E") (pin "2") (pinfunction "2_2") (pintype "passive"))
    )
    (net (code "44") (name "Net-(L_IR_EMIT-C)") (class "Default")
      (node (ref "L_IR_EMIT") (pin "K") (pinfunction "C_K") (pintype "passive"))
      (node (ref "R_L_E") (pin "2") (pinfunction "2_2") (pintype "passive"))
    )
    (net (code "45") (name "Net-(PWR_LED-PadA)") (class "Default")
      (node (ref "PWR_LED") (pin "A") (pinfunction "A_A") (pintype "passive"))
      (node (ref "R_PWR") (pin "1") (pinfunction "1_1") (pintype "passive"))
    )
    (net (code "46") (name "Net-(PWR_SWITCH-Pad2)") (class "Default")
      (node (ref "PWR_SWITCH") (pin "2") (pinfunction "2_2") (pintype "bidirectional"))
      (node (ref "U$7") (pin "+") (pinfunction "+_+") (pintype "bidirectional"))
    )
    (net (code "47") (name "Net-(RF_IR_EMIT-C)") (class "Default")
      (node (ref "RF_IR_EMIT") (pin "K") (pinfunction "C_K") (pintype "passive"))
      (node (ref "R_RF_E") (pin "2") (pinfunction "2_2") (pintype "passive"))
    )
    (net (code "48") (name "Net-(R_IR_EMIT-C)") (class "Default")
      (node (ref "R_IR_EMIT") (pin "K") (pinfunction "C_K") (pintype "passive"))
      (node (ref "R_R_E") (pin "2") (pinfunction "2_2") (pintype "passive"))
    )
    (net (code "49") (name "Net-(R_LF_E-Pad1)") (class "Default")
      (node (ref "R_LF_E") (pin "1") (pinfunction "1_1") (pintype "passive"))
      (node (ref "U$9") (pin "3C") (pinfunction "3C_3C") (pintype "bidirectional"))
      (node (ref "U$9") (pin "4C") (pinfunction "4C_4C") (pintype "bidirectional"))
    )
    (net (code "50") (name "Net-(R_L_E-Pad1)") (class "Default")
      (node (ref "R_L_E") (pin "1") (pinfunction "1_1") (pintype "passive"))
      (node (ref "U$9") (pin "2C") (pinfunction "2C_2C") (pintype "bidirectional"))
    )
    (net (code "51") (name "Net-(R_RF_E-Pad1)") (class "Default")
      (node (ref "R_RF_E") (pin "1") (pinfunction "1_1") (pintype "passive"))
      (node (ref "U$9") (pin "5C") (pinfunction "5C_5C") (pintype "bidirectional"))
      (node (ref "U$9") (pin "6C") (pinfunction "6C_6C") (pintype "bidirectional"))
    )
    (net (code "52") (name "Net-(R_R_E-Pad1)") (class "Default")
      (node (ref "R_R_E") (pin "1") (pinfunction "1_1") (pintype "passive"))
      (node (ref "U$9") (pin "7C") (pinfunction "7C_7C") (pintype "bidirectional"))
    )
    (net (code "53") (name "Net-(SPK1--)") (class "Default")
      (node (ref "D_B") (pin "A") (pinfunction "A_A") (pintype "passive"))
      (node (ref "SPK1") (pin "+") (pinfunction "-_+") (pintype "passive"))
      (node (ref "U$9") (pin "1C") (pinfunction "1C_1C") (pintype "bidirectional"))
    )
    (net (code "54") (name "Net-(U$3-VCAP1)") (class "Default")
      (node (ref "C_VCAP1") (pin "1") (pinfunction "1_1") (pintype "passive"))
      (node (ref "U$3") (pin "48") (pinfunction "VCAP1_48") (pintype "bidirectional"))
    )
    (net (code "55") (name "Net-(U$3-VCAP2)") (class "Default")
      (node (ref "C_VCAP2") (pin "1") (pinfunction "1_1") (pintype "passive"))
      (node (ref "U$3") (pin "73") (pinfunction "VCAP2_73") (pintype "bidirectional"))
    )
    (net (code "56") (name "Net-(U$7-Pad-)") (class "Default")
      (node (ref "U$7") (pin "-") (pinfunction "-_-") (pintype "bidirectional"))
      (node (ref "U$8") (pin "+") (pinfunction "+_+") (pintype "bidirectional"))
    )
    (net (code "57") (name "RENCA") (class "Default")
      (node (ref "R_MOT") (pin "1") (pinfunction "1_1") (pintype "passive"))
      (node (ref "U$3") (pin "43") (pinfunction "PE13_43") (pintype "bidirectional"))
    )
    (net (code "58") (name "RENCB") (class "Default")
      (node (ref "R_MOT") (pin "2") (pinfunction "2_2") (pintype "passive"))
      (node (ref "U$3") (pin "44") (pinfunction "PE14_44") (pintype "bidirectional"))
    )
    (net (code "59") (name "RESET") (class "Default")
      (node (ref "C_RESET1") (pin "1") (pinfunction "1_1") (pintype "passive"))
      (node (ref "RST") (pin "1") (pinfunction "S_1") (pintype "passive"))
      (node (ref "R_RST_UP1") (pin "1") (pinfunction "1_1") (pintype "passive"))
      (node (ref "U$3") (pin "14") (pinfunction "NRST_14") (pintype "bidirectional"))
    )
    (net (code "60") (name "RF_EMITTER") (class "Default")
      (node (ref "U$3") (pin "91") (pinfunction "PB5_91") (pintype "bidirectional"))
      (node (ref "U$9") (pin "2B") (pinfunction "2B_2B") (pintype "bidirectional"))
    )
    (net (code "61") (name "RF_REC") (class "Default")
      (node (ref "RF_REC") (pin "E") (pinfunction "E_E") (pintype "bidirectional"))
      (node (ref "R_RF_R") (pin "2") (pinfunction "2_2") (pintype "passive"))
      (node (ref "U$3") (pin "34") (pinfunction "PB0_34") (pintype "bidirectional"))
    )
    (net (code "62") (name "RIGHT_REC") (class "Default")
      (node (ref "R_REC") (pin "E") (pinfunction "E_E") (pintype "bidirectional"))
      (node (ref "R_R_R") (pin "2") (pinfunction "2_2") (pintype "passive"))
      (node (ref "U$3") (pin "35") (pinfunction "PB1_35") (pintype "bidirectional"))
    )
    (net (code "63") (name "RPWMA") (class "Default")
      (node (ref "MOS_R") (pin "IN_A") (pinfunction "IN_A_IN_A") (pintype "bidirectional"))
      (node (ref "R1_RMOT") (pin "2") (pinfunction "2_2") (pintype "passive"))
      (node (ref "U$3") (pin "24") (pinfunction "PA2_24") (pintype "bidirectional"))
    )
    (net (code "64") (name "RPWMB") (class "Default")
      (node (ref "MOS_R") (pin "IN_B") (pinfunction "IN_B_IN_B") (pintype "bidirectional"))
      (node (ref "R2_RMOT") (pin "2") (pinfunction "2_2") (pintype "passive"))
      (node (ref "U$3") (pin "25") (pinfunction "PA3_25") (pintype "bidirectional"))
    )
    (net (code "65") (name "RX") (class "Default")
      (node (ref "PROG_HEAD") (pin "5") (pinfunction "5_5") (pintype "passive"))
      (node (ref "U$3") (pin "69") (pinfunction "PA10_69") (pintype "bidirectional"))
    )
    (net (code "66") (name "R_EMITTER") (class "Default")
      (node (ref "U$3") (pin "90") (pinfunction "PB4_90") (pintype "bidirectional"))
      (node (ref "U$9") (pin "3B") (pinfunction "3B_3B") (pintype "bidirectional"))
      (node (ref "U$9") (pin "4B") (pinfunction "4B_4B") (pintype "bidirectional"))
    )
    (net (code "67") (name "SW1") (class "Default")
      (node (ref "C_S1") (pin "1") (pinfunction "1_1") (pintype "passive"))
      (node (ref "R_SW1") (pin "1") (pinfunction "1_1") (pintype "passive"))
      (node (ref "S1") (pin "1") (pinfunction "S_1") (pintype "passive"))
      (node (ref "U$3") (pin "63") (pinfunction "PC6_63") (pintype "bidirectional"))
    )
    (net (code "68") (name "SW2") (class "Default")
      (node (ref "C_S2") (pin "1") (pinfunction "1_1") (pintype "passive"))
      (node (ref "R_SW2") (pin "1") (pinfunction "1_1") (pintype "passive"))
      (node (ref "S2") (pin "1") (pinfunction "S_1") (pintype "passive"))
      (node (ref "U$3") (pin "62") (pinfunction "PD15_62") (pintype "bidirectional"))
    )
    (net (code "69") (name "SWCLK") (class "Default")
      (node (ref "PROG_HEAD") (pin "6") (pinfunction "6_6") (pintype "passive"))
      (node (ref "U$3") (pin "76") (pinfunction "PA14_76") (pintype "bidirectional"))
    )
    (net (code "70") (name "SWDIO") (class "Default")
      (node (ref "PROG_HEAD") (pin "8") (pinfunction "8_8") (pintype "passive"))
      (node (ref "U$3") (pin "72") (pinfunction "PA13_72") (pintype "bidirectional"))
    )
    (net (code "71") (name "TX") (class "Default")
      (node (ref "PROG_HEAD") (pin "7") (pinfunction "7_7") (pintype "passive"))
      (node (ref "U$3") (pin "68") (pinfunction "PA9_68") (pintype "bidirectional"))
    )
    (net (code "72") (name "V_BAT") (class "Default")
      (node (ref "50LDO") (pin "IN1") (pinfunction "IN1_IN1") (pintype "bidirectional"))
      (node (ref "50LDO") (pin "IN2") (pinfunction "IN2_IN2") (pintype "bidirectional"))
      (node (ref "C1_LMOT") (pin "2") (pinfunction "2_2") (pintype "passive"))
      (node (ref "C1_RMOT") (pin "2") (pinfunction "2_2") (pintype "passive"))
      (node (ref "C2_LMOT") (pin "2") (pinfunction "2_2") (pintype "passive"))
      (node (ref "C2_RMOT") (pin "2") (pinfunction "2_2") (pintype "passive"))
      (node (ref "C_VBAT1") (pin "1") (pinfunction "1_1") (pintype "passive"))
      (node (ref "C_VBAT2") (pin "1") (pinfunction "1_1") (pintype "passive"))
      (node (ref "HB_L") (pin "P1S/PS2") (pinfunction "P1S/P2S_P1S/PS2") (pintype "bidirectional"))
      (node (ref "HB_R") (pin "P1S/PS2") (pinfunction "P1S/P2S_P1S/PS2") (pintype "bidirectional"))
      (node (ref "MOS_L") (pin "VDD") (pinfunction "VDD_VDD") (pintype "bidirectional"))
      (node (ref "MOS_R") (pin "VDD") (pinfunction "VDD_VDD") (pintype "bidirectional"))
      (node (ref "PWR_SWITCH") (pin "3") (pinfunction "3_3") (pintype "bidirectional"))
    )
    (net (code "73") (name "unconnected-(50LDO-PadNC)") (class "Default")
      (node (ref "50LDO") (pin "NC") (pinfunction "NC_NC") (pintype "bidirectional"))
    )
    (net (code "74") (name "unconnected-(50LDO-PadPG)") (class "Default")
      (node (ref "50LDO") (pin "PG") (pinfunction "PG_PG") (pintype "bidirectional"))
    )
    (net (code "75") (name "unconnected-(BOOT0-P1-Pad4)") (class "Default")
      (node (ref "BOOT0") (pin "4") (pinfunction "P1_4") (pintype "passive"))
    )
    (net (code "76") (name "unconnected-(BOOT0-S1-Pad2)") (class "Default")
      (node (ref "BOOT0") (pin "2") (pinfunction "S1_2") (pintype "passive"))
    )
    (net (code "77") (name "unconnected-(HB_L-PadP1G)") (class "Default")
      (node (ref "HB_L") (pin "P1G") (pinfunction "P1G_P1G") (pintype "bidirectional"))
    )
    (net (code "78") (name "unconnected-(HB_R-PadP1G)") (class "Default")
      (node (ref "HB_R") (pin "P1G") (pinfunction "P1G_P1G") (pintype "bidirectional"))
    )
    (net (code "79") (name "unconnected-(MOS_L-PadNC1)") (class "Default")
      (node (ref "MOS_L") (pin "NC1") (pinfunction "NC1_NC1") (pintype "bidirectional"))
    )
    (net (code "80") (name "unconnected-(MOS_L-PadNC2)") (class "Default")
      (node (ref "MOS_L") (pin "NC2") (pinfunction "NC2_NC2") (pintype "bidirectional"))
    )
    (net (code "81") (name "unconnected-(MOS_R-PadNC1)") (class "Default")
      (node (ref "MOS_R") (pin "NC1") (pinfunction "NC1_NC1") (pintype "bidirectional"))
    )
    (net (code "82") (name "unconnected-(MOS_R-PadNC2)") (class "Default")
      (node (ref "MOS_R") (pin "NC2") (pinfunction "NC2_NC2") (pintype "bidirectional"))
    )
    (net (code "83") (name "unconnected-(PWR_SWITCH-Pad1)") (class "Default")
      (node (ref "PWR_SWITCH") (pin "1") (pinfunction "1_1") (pintype "bidirectional"))
    )
    (net (code "84") (name "unconnected-(RST-P1-Pad4)") (class "Default")
      (node (ref "RST") (pin "4") (pinfunction "P1_4") (pintype "passive"))
    )
    (net (code "85") (name "unconnected-(RST-S1-Pad2)") (class "Default")
      (node (ref "RST") (pin "2") (pinfunction "S1_2") (pintype "passive"))
    )
    (net (code "86") (name "unconnected-(S1-P1-Pad4)") (class "Default")
      (node (ref "S1") (pin "4") (pinfunction "P1_4") (pintype "passive"))
    )
    (net (code "87") (name "unconnected-(S1-S1-Pad2)") (class "Default")
      (node (ref "S1") (pin "2") (pinfunction "S1_2") (pintype "passive"))
    )
    (net (code "88") (name "unconnected-(S2-P1-Pad4)") (class "Default")
      (node (ref "S2") (pin "4") (pinfunction "P1_4") (pintype "passive"))
    )
    (net (code "89") (name "unconnected-(S2-S1-Pad2)") (class "Default")
      (node (ref "S2") (pin "2") (pinfunction "S1_2") (pintype "passive"))
    )
    (net (code "90") (name "unconnected-(U$3-PA8-Pad67)") (class "Default")
      (node (ref "U$3") (pin "67") (pinfunction "PA8_67") (pintype "bidirectional"))
    )
    (net (code "91") (name "unconnected-(U$3-PA11-Pad70)") (class "Default")
      (node (ref "U$3") (pin "70") (pinfunction "PA11_70") (pintype "bidirectional"))
    )
    (net (code "92") (name "unconnected-(U$3-PA12-Pad71)") (class "Default")
      (node (ref "U$3") (pin "71") (pinfunction "PA12_71") (pintype "bidirectional"))
    )
    (net (code "93") (name "unconnected-(U$3-PA15-Pad77)") (class "Default")
      (node (ref "U$3") (pin "77") (pinfunction "PA15_77") (pintype "bidirectional"))
    )
    (net (code "94") (name "unconnected-(U$3-PB2-Pad36)") (class "Default")
      (node (ref "U$3") (pin "36") (pinfunction "PB2_36") (pintype "bidirectional"))
    )
    (net (code "95") (name "unconnected-(U$3-PB3-Pad89)") (class "Default")
      (node (ref "U$3") (pin "89") (pinfunction "PB3_89") (pintype "bidirectional"))
    )
    (net (code "96") (name "unconnected-(U$3-PB6-Pad92)") (class "Default")
      (node (ref "U$3") (pin "92") (pinfunction "PB6_92") (pintype "bidirectional"))
    )
    (net (code "97") (name "unconnected-(U$3-PB7-Pad93)") (class "Default")
      (node (ref "U$3") (pin "93") (pinfunction "PB7_93") (pintype "bidirectional"))
    )
    (net (code "98") (name "unconnected-(U$3-PB8-Pad95)") (class "Default")
      (node (ref "U$3") (pin "95") (pinfunction "PB8_95") (pintype "bidirectional"))
    )
    (net (code "99") (name "unconnected-(U$3-PB9-Pad96)") (class "Default")
      (node (ref "U$3") (pin "96") (pinfunction "PB9_96") (pintype "bidirectional"))
    )
    (net (code "100") (name "unconnected-(U$3-PB10-Pad46)") (class "Default")
      (node (ref "U$3") (pin "46") (pinfunction "PB10_46") (pintype "bidirectional"))
    )
    (net (code "101") (name "unconnected-(U$3-PB11-Pad47)") (class "Default")
      (node (ref "U$3") (pin "47") (pinfunction "PB11_47") (pintype "bidirectional"))
    )
    (net (code "102") (name "unconnected-(U$3-PB12-Pad51)") (class "Default")
      (node (ref "U$3") (pin "51") (pinfunction "PB12_51") (pintype "bidirectional"))
    )
    (net (code "103") (name "unconnected-(U$3-PB13-Pad52)") (class "Default")
      (node (ref "U$3") (pin "52") (pinfunction "PB13_52") (pintype "bidirectional"))
    )
    (net (code "104") (name "unconnected-(U$3-PB14-Pad53)") (class "Default")
      (node (ref "U$3") (pin "53") (pinfunction "PB14_53") (pintype "bidirectional"))
    )
    (net (code "105") (name "unconnected-(U$3-PB15-Pad54)") (class "Default")
      (node (ref "U$3") (pin "54") (pinfunction "PB15_54") (pintype "bidirectional"))
    )
    (net (code "106") (name "unconnected-(U$3-PC0-Pad15)") (class "Default")
      (node (ref "U$3") (pin "15") (pinfunction "PC0_15") (pintype "bidirectional"))
    )
    (net (code "107") (name "unconnected-(U$3-PC1-Pad16)") (class "Default")
      (node (ref "U$3") (pin "16") (pinfunction "PC1_16") (pintype "bidirectional"))
    )
    (net (code "108") (name "unconnected-(U$3-PC2-Pad17)") (class "Default")
      (node (ref "U$3") (pin "17") (pinfunction "PC2_17") (pintype "bidirectional"))
    )
    (net (code "109") (name "unconnected-(U$3-PC3-Pad18)") (class "Default")
      (node (ref "U$3") (pin "18") (pinfunction "PC3_18") (pintype "bidirectional"))
    )
    (net (code "110") (name "unconnected-(U$3-PC7-Pad64)") (class "Default")
      (node (ref "U$3") (pin "64") (pinfunction "PC7_64") (pintype "bidirectional"))
    )
    (net (code "111") (name "unconnected-(U$3-PC10-Pad78)") (class "Default")
      (node (ref "U$3") (pin "78") (pinfunction "PC10_78") (pintype "bidirectional"))
    )
    (net (code "112") (name "unconnected-(U$3-PC11-Pad79)") (class "Default")
      (node (ref "U$3") (pin "79") (pinfunction "PC11_79") (pintype "bidirectional"))
    )
    (net (code "113") (name "unconnected-(U$3-PC12-Pad80)") (class "Default")
      (node (ref "U$3") (pin "80") (pinfunction "PC12_80") (pintype "bidirectional"))
    )
    (net (code "114") (name "unconnected-(U$3-PC13-ANTI_TAMP-Pad7)") (class "Default")
      (node (ref "U$3") (pin "7") (pinfunction "PC13-ANTI_TAMP_7") (pintype "bidirectional"))
    )
    (net (code "115") (name "unconnected-(U$3-PC14-OSC32_IN-Pad8)") (class "Default")
      (node (ref "U$3") (pin "8") (pinfunction "PC14-OSC32_IN_8") (pintype "bidirectional"))
    )
    (net (code "116") (name "unconnected-(U$3-PC15-OSC32_OUT-Pad9)") (class "Default")
      (node (ref "U$3") (pin "9") (pinfunction "PC15-OSC32_OUT_9") (pintype "bidirectional"))
    )
    (net (code "117") (name "unconnected-(U$3-PD0-Pad81)") (class "Default")
      (node (ref "U$3") (pin "81") (pinfunction "PD0_81") (pintype "bidirectional"))
    )
    (net (code "118") (name "unconnected-(U$3-PD6-Pad87)") (class "Default")
      (node (ref "U$3") (pin "87") (pinfunction "PD6_87") (pintype "bidirectional"))
    )
    (net (code "119") (name "unconnected-(U$3-PD7-Pad88)") (class "Default")
      (node (ref "U$3") (pin "88") (pinfunction "PD7_88") (pintype "bidirectional"))
    )
    (net (code "120") (name "unconnected-(U$3-PD8-Pad55)") (class "Default")
      (node (ref "U$3") (pin "55") (pinfunction "PD8_55") (pintype "bidirectional"))
    )
    (net (code "121") (name "unconnected-(U$3-PD9-Pad56)") (class "Default")
      (node (ref "U$3") (pin "56") (pinfunction "PD9_56") (pintype "bidirectional"))
    )
    (net (code "122") (name "unconnected-(U$3-PD10-Pad57)") (class "Default")
      (node (ref "U$3") (pin "57") (pinfunction "PD10_57") (pintype "bidirectional"))
    )
    (net (code "123") (name "unconnected-(U$3-PD11-Pad58)") (class "Default")
      (node (ref "U$3") (pin "58") (pinfunction "PD11_58") (pintype "bidirectional"))
    )
    (net (code "124") (name "unconnected-(U$3-PD13-Pad60)") (class "Default")
      (node (ref "U$3") (pin "60") (pinfunction "PD13_60") (pintype "bidirectional"))
    )
    (net (code "125") (name "unconnected-(U$3-PD14-Pad61)") (class "Default")
      (node (ref "U$3") (pin "61") (pinfunction "PD14_61") (pintype "bidirectional"))
    )
    (net (code "126") (name "unconnected-(U$3-PE0-Pad97)") (class "Default")
      (node (ref "U$3") (pin "97") (pinfunction "PE0_97") (pintype "bidirectional"))
    )
    (net (code "127") (name "unconnected-(U$3-PE1-Pad98)") (class "Default")
      (node (ref "U$3") (pin "98") (pinfunction "PE1_98") (pintype "bidirectional"))
    )
    (net (code "128") (name "unconnected-(U$3-PE2-Pad1)") (class "Default")
      (node (ref "U$3") (pin "1") (pinfunction "PE2_1") (pintype "bidirectional"))
    )
    (net (code "129") (name "unconnected-(U$3-PE3-Pad2)") (class "Default")
      (node (ref "U$3") (pin "2") (pinfunction "PE3_2") (pintype "bidirectional"))
    )
    (net (code "130") (name "unconnected-(U$3-PE4-Pad3)") (class "Default")
      (node (ref "U$3") (pin "3") (pinfunction "PE4_3") (pintype "bidirectional"))
    )
    (net (code "131") (name "unconnected-(U$3-PE5-Pad4)") (class "Default")
      (node (ref "U$3") (pin "4") (pinfunction "PE5_4") (pintype "bidirectional"))
    )
    (net (code "132") (name "unconnected-(U$3-PE6-Pad5)") (class "Default")
      (node (ref "U$3") (pin "5") (pinfunction "PE6_5") (pintype "bidirectional"))
    )
    (net (code "133") (name "unconnected-(U$3-PE7-Pad37)") (class "Default")
      (node (ref "U$3") (pin "37") (pinfunction "PE7_37") (pintype "bidirectional"))
    )
    (net (code "134") (name "unconnected-(U$3-PE8-Pad38)") (class "Default")
      (node (ref "U$3") (pin "38") (pinfunction "PE8_38") (pintype "bidirectional"))
    )
    (net (code "135") (name "unconnected-(U$3-PE10-Pad40)") (class "Default")
      (node (ref "U$3") (pin "40") (pinfunction "PE10_40") (pintype "bidirectional"))
    )
    (net (code "136") (name "unconnected-(U$3-PE12-Pad42)") (class "Default")
      (node (ref "U$3") (pin "42") (pinfunction "PE12_42") (pintype "bidirectional"))
    )
    (net (code "137") (name "unconnected-(U$3-PE15-Pad45)") (class "Default")
      (node (ref "U$3") (pin "45") (pinfunction "PE15_45") (pintype "bidirectional"))
    )
    (net (code "138") (name "unconnected-(U$3-PH0-OSC_IN-Pad12)") (class "Default")
      (node (ref "U$3") (pin "12") (pinfunction "PH0-OSC_IN_12") (pintype "bidirectional"))
    )
    (net (code "139") (name "unconnected-(U$3-PH1-OSC_OUT-Pad13)") (class "Default")
      (node (ref "U$3") (pin "13") (pinfunction "PH1-OSC_OUT_13") (pintype "bidirectional"))
    )
    (net (code "140") (name "unconnected-(U$9-PadCOM)") (class "Default")
      (node (ref "U$9") (pin "COM") (pinfunction "COM_COM") (pintype "bidirectional"))
    )
  )
)
